# LT6813.net
KiCad netlist of a schematic drawn in Altium Designer
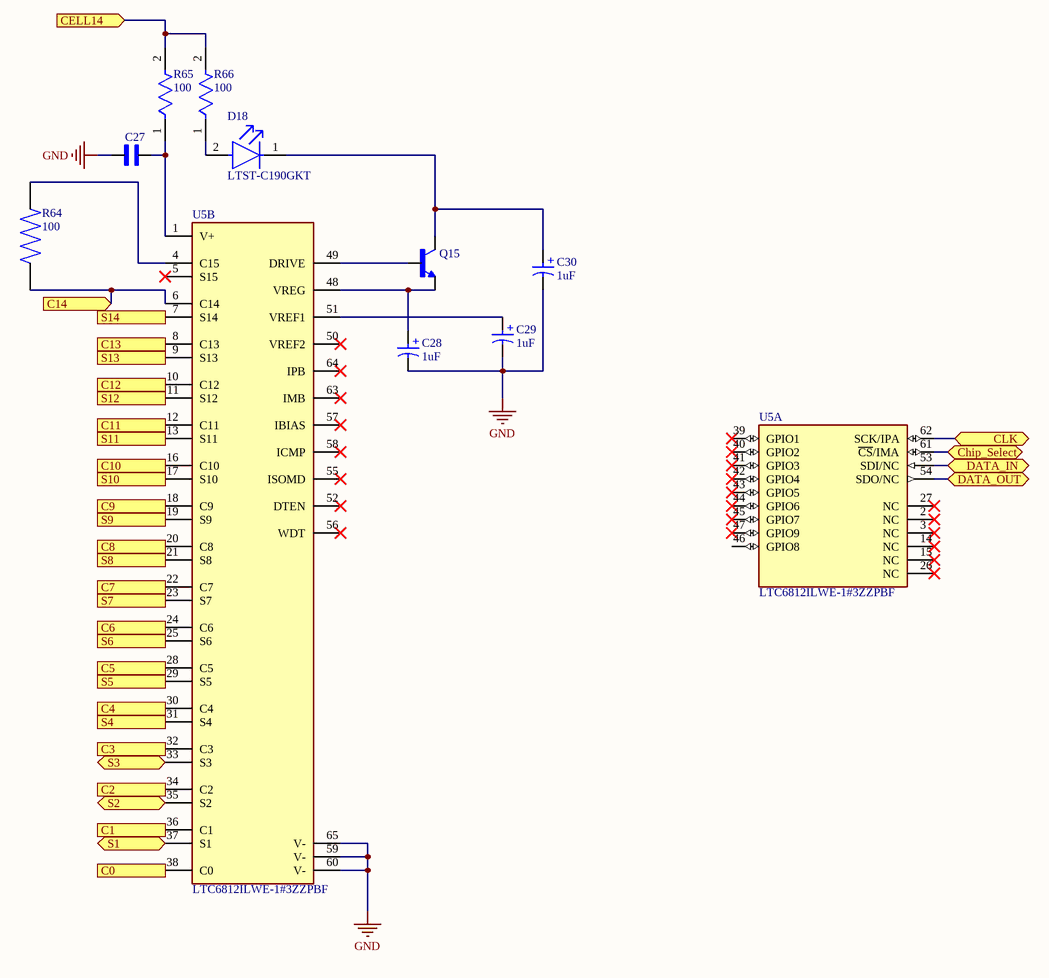
[diagram p0: LT6813.SchDoc]

(export (version "E")
  (design (tool "Eeschema 10.0.6"))
  (components
    (comp (ref "C27")
      (value "GRM155R71C104KA88D")
      (footprint "CAPC1005X55N")
      (description "CAP CER 0.1UF 16V 10% X7R 0402")
      (fields (field (name "MF") "{'manufacturer': u'Murata'}"))
      (libsource (lib "SnapEDA_Library") (part "GRM155R71C104KA88D"))
    )
    (comp (ref "C28")
      (value "1uF")
      (footprint "WCAP-ASLI_D4H5.5")
      (description "865080840001 Cap, 1Uf, 20%, 100V, Alu Elec Smd Rohs Compliant: Yes")
      (libsource (lib "Altium Content Vault") (part "Capacitor_Polarized"))
    )
    (comp (ref "C29")
      (value "1uF")
      (footprint "WCAP-ASLI_D4H5.5")
      (description "865080840001 Cap, 1Uf, 20%, 100V, Alu Elec Smd Rohs Compliant: Yes")
      (libsource (lib "Altium Content Vault") (part "Capacitor_Polarized"))
    )
    (comp (ref "C30")
      (value "1uF")
      (footprint "WCAP-ASLI_D4H5.5")
      (description "865080840001 Cap, 1Uf, 20%, 100V, Alu Elec Smd Rohs Compliant: Yes")
      (libsource (lib "Altium Content Vault") (part "Capacitor_Polarized"))
    )
    (comp (ref "D18")
      (value "LTST-C190GKT")
      (footprint "FP-LTST-C190GKT-MFG")
      (description "LED GREEN CLEAR CHIP SMD")
      (fields (field (name "VOLTAGE") "2V"))
      (libsource (lib "Altium Content Vault") (part "8706943c75ba83719d021d2fdc84c58"))
    )
    (comp (ref "Q15")
      (value "DXT5551P5-13")
      (footprint "TRANS_DXT5551P5-13")
      (fields (field (name "MF") "{'manufacturer': u'Diodes Inc.'}"))
      (libsource (lib "SnapEDA_Library") (part "DXT5551P5-13"))
    )
    (comp (ref "R64")
      (value "100")
      (footprint "RES_ERJ2RKF1000X")
      (fields (field (name "MF") "{'manufacturer': u'Panasonic'}") (field (name "MP") "ERJ2RKF1000X"))
      (libsource (lib "SnapEDA_Library") (part "ERJ2RKF1000X"))
    )
    (comp (ref "R65")
      (value "100")
      (footprint "FP-CRCW0402-e3-IPC_C")
      (description "RES Thick Film, 100Ω, 1%, 0.063W, 100ppm/°C, 0402")
      (fields (field (name "TOLERANCE") "1%"))
      (libsource (lib "Altium Content Vault") (part "1029c3af85768c4190bb7ad29bc67b5"))
    )
    (comp (ref "R66")
      (value "100")
      (footprint "FP-CRCW0402-e3-IPC_C")
      (description "RES Thick Film, 100Ω, 1%, 0.063W, 100ppm/°C, 0402")
      (fields (field (name "TOLERANCE") "1%"))
      (libsource (lib "Altium Content Vault") (part "1029c3af85768c4190bb7ad29bc67b5"))
    )
    (comp (ref "U5")
      (value "LTC6812ILWE-1#3ZZPBF")
      (footprint "FP-LWE-64-05-08-1982-MFG")
      (description "MULTICELL BAT MON S")
      (fields
        (field (name "MANUFACTURER") "Analog Devices")
        (field (name "OCTOPART") "https://octopart.com/ltc6812ilwe-1%233zzpbf-analog+devices-97359568")
      )
      (libsource (lib "Altium Content Vault") (part "304f8939b11d0bec79fdbed9c933bb7"))
    )
  )
  (nets
    (net (code "1") (name "/C0") (class "Default")
      (node (ref "U5") (pin "38") (pinfunction "C0_38") (pintype "passive"))
    )
    (net (code "2") (name "/C1") (class "Default")
      (node (ref "U5") (pin "36") (pinfunction "C1_36") (pintype "passive"))
    )
    (net (code "3") (name "/C2") (class "Default")
      (node (ref "U5") (pin "34") (pinfunction "C2_34") (pintype "passive"))
    )
    (net (code "4") (name "/C3") (class "Default")
      (node (ref "U5") (pin "32") (pinfunction "C3_32") (pintype "passive"))
    )
    (net (code "5") (name "/C4") (class "Default")
      (node (ref "U5") (pin "30") (pinfunction "C4_30") (pintype "passive"))
    )
    (net (code "6") (name "/C5") (class "Default")
      (node (ref "U5") (pin "28") (pinfunction "C5_28") (pintype "passive"))
    )
    (net (code "7") (name "/C6") (class "Default")
      (node (ref "U5") (pin "24") (pinfunction "C6_24") (pintype "passive"))
    )
    (net (code "8") (name "/C7") (class "Default")
      (node (ref "U5") (pin "22") (pinfunction "C7_22") (pintype "passive"))
    )
    (net (code "9") (name "/C8") (class "Default")
      (node (ref "U5") (pin "20") (pinfunction "C8_20") (pintype "passive"))
    )
    (net (code "10") (name "/C9") (class "Default")
      (node (ref "U5") (pin "18") (pinfunction "C9_18") (pintype "passive"))
    )
    (net (code "11") (name "/C10") (class "Default")
      (node (ref "U5") (pin "16") (pinfunction "C10_16") (pintype "passive"))
    )
    (net (code "12") (name "/C11") (class "Default")
      (node (ref "U5") (pin "12") (pinfunction "C11_12") (pintype "passive"))
    )
    (net (code "13") (name "/C12") (class "Default")
      (node (ref "U5") (pin "10") (pinfunction "C12_10") (pintype "passive"))
    )
    (net (code "14") (name "/C13") (class "Default")
      (node (ref "U5") (pin "8") (pinfunction "C13_8") (pintype "passive"))
    )
    (net (code "15") (name "/C14") (class "Default")
      (node (ref "R64") (pin "1") (pinfunction "1_1") (pintype "passive"))
      (node (ref "U5") (pin "6") (pinfunction "C14_6") (pintype "passive"))
    )
    (net (code "16") (name "/CELL14") (class "Default")
      (node (ref "R65") (pin "2") (pinfunction "2_2") (pintype "passive"))
      (node (ref "R66") (pin "2") (pinfunction "2_2") (pintype "passive"))
    )
    (net (code "17") (name "/CLK") (class "Default")
      (node (ref "U5") (pin "62") (pinfunction "SCK/IPA_62") (pintype "bidirectional"))
    )
    (net (code "18") (name "/Chip_Select") (class "Default")
      (node (ref "U5") (pin "61") (pinfunction "~{CS}/IMA_61") (pintype "bidirectional"))
    )
    (net (code "19") (name "/DATA_IN") (class "Default")
      (node (ref "U5") (pin "53") (pinfunction "SDI/NC_53") (pintype "input"))
    )
    (net (code "20") (name "/DATA_OUT") (class "Default")
      (node (ref "U5") (pin "54") (pinfunction "SDO/NC_54") (pintype "output"))
    )
    (net (code "21") (name "/S1") (class "Default")
      (node (ref "U5") (pin "37") (pinfunction "S1_37") (pintype "passive"))
    )
    (net (code "22") (name "/S2") (class "Default")
      (node (ref "U5") (pin "35") (pinfunction "S2_35") (pintype "passive"))
    )
    (net (code "23") (name "/S3") (class "Default")
      (node (ref "U5") (pin "33") (pinfunction "S3_33") (pintype "passive"))
    )
    (net (code "24") (name "/S4") (class "Default")
      (node (ref "U5") (pin "31") (pinfunction "S4_31") (pintype "passive"))
    )
    (net (code "25") (name "/S5") (class "Default")
      (node (ref "U5") (pin "29") (pinfunction "S5_29") (pintype "passive"))
    )
    (net (code "26") (name "/S6") (class "Default")
      (node (ref "U5") (pin "25") (pinfunction "S6_25") (pintype "passive"))
    )
    (net (code "27") (name "/S7") (class "Default")
      (node (ref "U5") (pin "23") (pinfunction "S7_23") (pintype "passive"))
    )
    (net (code "28") (name "/S8") (class "Default")
      (node (ref "U5") (pin "21") (pinfunction "S8_21") (pintype "passive"))
    )
    (net (code "29") (name "/S9") (class "Default")
      (node (ref "U5") (pin "19") (pinfunction "S9_19") (pintype "passive"))
    )
    (net (code "30") (name "/S10") (class "Default")
      (node (ref "U5") (pin "17") (pinfunction "S10_17") (pintype "passive"))
    )
    (net (code "31") (name "/S11") (class "Default")
      (node (ref "U5") (pin "13") (pinfunction "S11_13") (pintype "passive"))
    )
    (net (code "32") (name "/S12") (class "Default")
      (node (ref "U5") (pin "11") (pinfunction "S12_11") (pintype "passive"))
    )
    (net (code "33") (name "/S13") (class "Default")
      (node (ref "U5") (pin "9") (pinfunction "S13_9") (pintype "passive"))
    )
    (net (code "34") (name "/S14") (class "Default")
      (node (ref "U5") (pin "7") (pinfunction "S14_7") (pintype "passive"))
    )
    (net (code "35") (name "GND") (class "Default")
      (node (ref "C27") (pin "1") (pinfunction "1_1") (pintype "passive"))
      (node (ref "C28") (pin "2") (pinfunction "N_2") (pintype "passive"))
      (node (ref "C29") (pin "2") (pinfunction "N_2") (pintype "passive"))
      (node (ref "C30") (pin "2") (pinfunction "N_2") (pintype "passive"))
      (node (ref "U5") (pin "59") (pinfunction "V-_59") (pintype "power_in"))
      (node (ref "U5") (pin "60") (pinfunction "V-_60") (pintype "power_in"))
      (node (ref "U5") (pin "65") (pinfunction "V-_65") (pintype "power_in"))
    )
    (net (code "36") (name "Net-(C28-P)") (class "Default")
      (node (ref "C28") (pin "1") (pinfunction "P_1") (pintype "passive"))
      (node (ref "Q15") (pin "E") (pinfunction "E_E") (pintype "passive"))
      (node (ref "U5") (pin "48") (pinfunction "VREG_48") (pintype "passive"))
    )
    (net (code "37") (name "Net-(C29-P)") (class "Default")
      (node (ref "C29") (pin "1") (pinfunction "P_1") (pintype "passive"))
      (node (ref "U5") (pin "51") (pinfunction "VREF1_51") (pintype "passive"))
    )
    (net (code "38") (name "Net-(C30-P)") (class "Default")
      (node (ref "C30") (pin "1") (pinfunction "P_1") (pintype "passive"))
      (node (ref "D18") (pin "1") (pinfunction "C_1") (pintype "passive"))
      (node (ref "Q15") (pin "C") (pinfunction "C_C") (pintype "passive"))
    )
    (net (code "39") (name "Net-(D18-A)") (class "Default")
      (node (ref "D18") (pin "2") (pinfunction "A_2") (pintype "passive"))
      (node (ref "R66") (pin "1") (pinfunction "1_1") (pintype "passive"))
    )
    (net (code "40") (name "Net-(U5B-C15)") (class "Default")
      (node (ref "R64") (pin "2") (pinfunction "2_2") (pintype "passive"))
      (node (ref "U5") (pin "4") (pinfunction "C15_4") (pintype "passive"))
    )
    (net (code "41") (name "Net-(U5B-DRIVE)") (class "Default")
      (node (ref "Q15") (pin "B") (pinfunction "B_B") (pintype "passive"))
      (node (ref "U5") (pin "49") (pinfunction "DRIVE_49") (pintype "passive"))
    )
    (net (code "42") (name "Net-(U5B-V+)") (class "Default")
      (node (ref "C27") (pin "2") (pinfunction "2_2") (pintype "passive"))
      (node (ref "R65") (pin "1") (pinfunction "1_1") (pintype "passive"))
      (node (ref "U5") (pin "1") (pinfunction "V+_1") (pintype "power_in"))
    )
    (net (code "43") (name "unconnected-(U5A-GPIO1-Pad39)") (class "Default")
      (node (ref "U5") (pin "39") (pinfunction "GPIO1_39") (pintype "bidirectional+no_connect"))
    )
    (net (code "44") (name "unconnected-(U5A-GPIO2-Pad40)") (class "Default")
      (node (ref "U5") (pin "40") (pinfunction "GPIO2_40") (pintype "bidirectional+no_connect"))
    )
    (net (code "45") (name "unconnected-(U5A-GPIO3-Pad41)") (class "Default")
      (node (ref "U5") (pin "41") (pinfunction "GPIO3_41") (pintype "bidirectional+no_connect"))
    )
    (net (code "46") (name "unconnected-(U5A-GPIO4-Pad42)") (class "Default")
      (node (ref "U5") (pin "42") (pinfunction "GPIO4_42") (pintype "bidirectional+no_connect"))
    )
    (net (code "47") (name "unconnected-(U5A-GPIO5-Pad43)") (class "Default")
      (node (ref "U5") (pin "43") (pinfunction "GPIO5_43") (pintype "bidirectional+no_connect"))
    )
    (net (code "48") (name "unconnected-(U5A-GPIO6-Pad44)") (class "Default")
      (node (ref "U5") (pin "44") (pinfunction "GPIO6_44") (pintype "bidirectional+no_connect"))
    )
    (net (code "49") (name "unconnected-(U5A-GPIO7-Pad45)") (class "Default")
      (node (ref "U5") (pin "45") (pinfunction "GPIO7_45") (pintype "bidirectional+no_connect"))
    )
    (net (code "50") (name "unconnected-(U5A-GPIO8-Pad46)") (class "Default")
      (node (ref "U5") (pin "46") (pinfunction "GPIO8_46") (pintype "bidirectional"))
    )
    (net (code "51") (name "unconnected-(U5A-GPIO9-Pad47)") (class "Default")
      (node (ref "U5") (pin "47") (pinfunction "GPIO9_47") (pintype "bidirectional+no_connect"))
    )
    (net (code "52") (name "unconnected-(U5A-NC-Pad2)") (class "Default")
      (node (ref "U5") (pin "2") (pinfunction "NC_2") (pintype "passive+no_connect"))
    )
    (net (code "53") (name "unconnected-(U5A-NC-Pad3)") (class "Default")
      (node (ref "U5") (pin "3") (pinfunction "NC_3") (pintype "passive+no_connect"))
    )
    (net (code "54") (name "unconnected-(U5A-NC-Pad14)") (class "Default")
      (node (ref "U5") (pin "14") (pinfunction "NC_14") (pintype "passive+no_connect"))
    )
    (net (code "55") (name "unconnected-(U5A-NC-Pad15)") (class "Default")
      (node (ref "U5") (pin "15") (pinfunction "NC_15") (pintype "passive+no_connect"))
    )
    (net (code "56") (name "unconnected-(U5A-NC-Pad26)") (class "Default")
      (node (ref "U5") (pin "26") (pinfunction "NC_26") (pintype "passive+no_connect"))
    )
    (net (code "57") (name "unconnected-(U5A-NC-Pad27)") (class "Default")
      (node (ref "U5") (pin "27") (pinfunction "NC_27") (pintype "passive+no_connect"))
    )
    (net (code "58") (name "unconnected-(U5B-DTEN-Pad52)") (class "Default")
      (node (ref "U5") (pin "52") (pinfunction "DTEN_52") (pintype "passive+no_connect"))
    )
    (net (code "59") (name "unconnected-(U5B-IBIAS-Pad57)") (class "Default")
      (node (ref "U5") (pin "57") (pinfunction "IBIAS_57") (pintype "passive+no_connect"))
    )
    (net (code "60") (name "unconnected-(U5B-ICMP-Pad58)") (class "Default")
      (node (ref "U5") (pin "58") (pinfunction "ICMP_58") (pintype "passive+no_connect"))
    )
    (net (code "61") (name "unconnected-(U5B-IMB-Pad63)") (class "Default")
      (node (ref "U5") (pin "63") (pinfunction "IMB_63") (pintype "passive+no_connect"))
    )
    (net (code "62") (name "unconnected-(U5B-IPB-Pad64)") (class "Default")
      (node (ref "U5") (pin "64") (pinfunction "IPB_64") (pintype "passive+no_connect"))
    )
    (net (code "63") (name "unconnected-(U5B-ISOMD-Pad55)") (class "Default")
      (node (ref "U5") (pin "55") (pinfunction "ISOMD_55") (pintype "passive+no_connect"))
    )
    (net (code "64") (name "unconnected-(U5B-S15-Pad5)") (class "Default")
      (node (ref "U5") (pin "5") (pinfunction "S15_5") (pintype "passive+no_connect"))
    )
    (net (code "65") (name "unconnected-(U5B-VREF2-Pad50)") (class "Default")
      (node (ref "U5") (pin "50") (pinfunction "VREF2_50") (pintype "passive+no_connect"))
    )
    (net (code "66") (name "unconnected-(U5B-WDT-Pad56)") (class "Default")
      (node (ref "U5") (pin "56") (pinfunction "WDT_56") (pintype "open_collector+no_connect"))
    )
  )
)
